# Scoreboard_Wifi_Controller_20170514.net
KiCad netlist of a schematic drawn in EAGLE
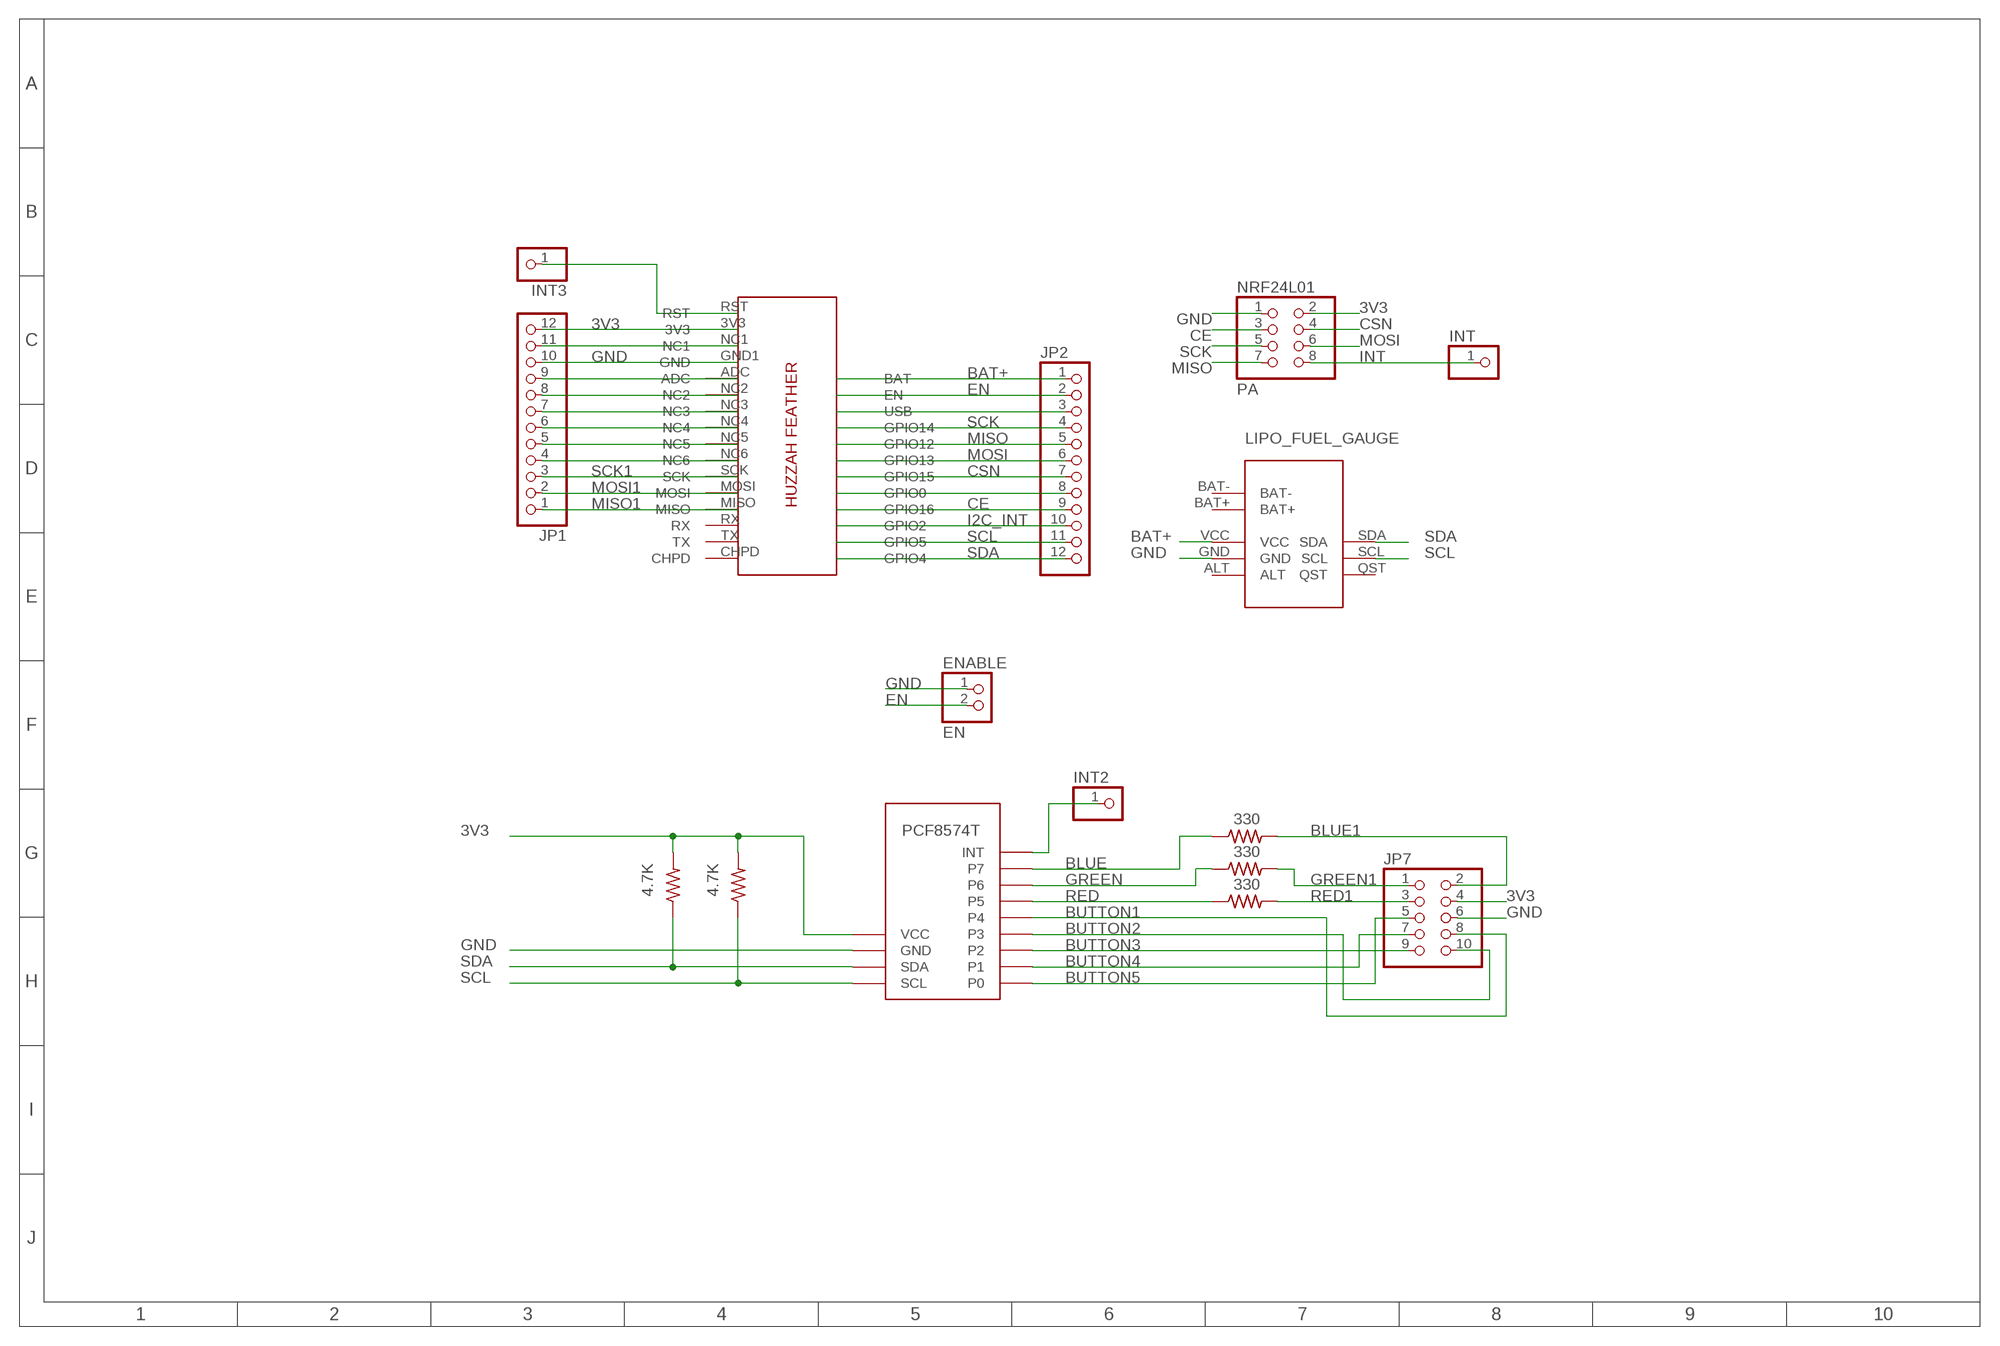
[diagram p0: schematic, sheet 1]

(export (version "E")
  (design (tool "Eeschema 10.0.6"))
  (components
    (comp (ref "ENABLE")
      (value "EN")
      (footprint "eagle-import:1X02_90")
      (libsource (lib "eagle-import") (part "PINHD-1X2/90"))
    )
    (comp (ref "INT")
      (value "PINHD-1X1CB")
      (footprint "eagle-import:1X01-CLEANBIG")
      (libsource (lib "eagle-import") (part "PINHD-1X1CB"))
    )
    (comp (ref "INT2")
      (value "PINHD-1X1CB")
      (footprint "eagle-import:1X01-CLEANBIG")
      (libsource (lib "eagle-import") (part "PINHD-1X1CB"))
    )
    (comp (ref "INT3")
      (value "PINHD-1X1CB")
      (footprint "eagle-import:1X01-CLEANBIG")
      (libsource (lib "eagle-import") (part "PINHD-1X1CB"))
    )
    (comp (ref "JP1")
      (value "PINHD-1X12-CB")
      (footprint "eagle-import:1X12-CB")
      (libsource (lib "eagle-import") (part "PINHD-1X12-CB"))
    )
    (comp (ref "JP2")
      (value "PINHD-1X12-CB")
      (footprint "eagle-import:1X12-CB")
      (libsource (lib "eagle-import") (part "PINHD-1X12-CB"))
    )
    (comp (ref "JP7")
      (value "PINHD-2X5/90")
      (footprint "eagle-import:2X05_90")
      (libsource (lib "eagle-import") (part "PINHD-2X5/90"))
    )
    (comp (ref "LIPO_FUEL_GAUGE")
      (value "LIPO_FUEL_GAUGE")
      (footprint "eagle-import:LIPO_FUEL_GAUGE")
      (libsource (lib "eagle-import") (part "LIPO_FUEL_GAUGE"))
    )
    (comp (ref "NRF24L01")
      (value "PA")
      (footprint "eagle-import:2X04_90")
      (libsource (lib "eagle-import") (part "PINHD-2X4/90"))
    )
    (comp (ref "R2")
      (value "330")
      (footprint "eagle-import:0207_10")
      (libsource (lib "eagle-import") (part "R-US_0207/10"))
    )
    (comp (ref "R3")
      (value "330")
      (footprint "eagle-import:0207_10")
      (libsource (lib "eagle-import") (part "R-US_0207/10"))
    )
    (comp (ref "R4")
      (value "330")
      (footprint "eagle-import:0207_10")
      (libsource (lib "eagle-import") (part "R-US_0207/10"))
    )
    (comp (ref "R5")
      (value "4.7K")
      (footprint "eagle-import:0207_10")
      (libsource (lib "eagle-import") (part "R-US_0207/10"))
    )
    (comp (ref "R6")
      (value "4.7K")
      (footprint "eagle-import:0207_10")
      (libsource (lib "eagle-import") (part "R-US_0207/10"))
    )
    (comp (ref "U$1")
      (value "ADAFRUIT-FEATHER-ESP8266-HUZZAHALT")
      (footprint "eagle-import:ADAFRUIT-FEATHER-ESP8266-HUZZAH-ALT")
      (libsource (lib "eagle-import") (part "ADAFRUIT-FEATHER-ESP8266-HUZZAHALT"))
    )
    (comp (ref "U$3")
      (value "PCF8574T_IO_EXPANDER")
      (footprint "eagle-import:PCF8574T_IO_EXPANDER")
      (libsource (lib "eagle-import") (part "PCF8574T_IO_EXPANDER"))
    )
  )
  (nets
    (net (code "1") (name "/3V3") (class "Default")
      (node (ref "JP1") (pin "12") (pinfunction "12_12") (pintype "passive"))
      (node (ref "JP7") (pin "4") (pinfunction "4_4") (pintype "passive"))
      (node (ref "NRF24L01") (pin "2") (pinfunction "2_2") (pintype "passive"))
      (node (ref "R5") (pin "2") (pinfunction "2_2") (pintype "passive"))
      (node (ref "R6") (pin "2") (pinfunction "2_2") (pintype "passive"))
      (node (ref "U$1") (pin "3V3") (pinfunction "3V3_3V3") (pintype "bidirectional"))
      (node (ref "U$3") (pin "VCC") (pinfunction "VCC_VCC") (pintype "input"))
    )
    (net (code "2") (name "/BAT+") (class "Default")
      (node (ref "JP2") (pin "1") (pinfunction "1_1") (pintype "passive"))
      (node (ref "LIPO_FUEL_GAUGE") (pin "VCC") (pinfunction "VCC_VCC") (pintype "bidirectional"))
      (node (ref "U$1") (pin "BAT") (pinfunction "BAT_BAT") (pintype "bidirectional"))
    )
    (net (code "3") (name "/BLUE") (class "Default")
      (node (ref "R2") (pin "1") (pinfunction "1_1") (pintype "passive"))
      (node (ref "U$3") (pin "P$7") (pinfunction "P7_P$7") (pintype "bidirectional"))
    )
    (net (code "4") (name "/BLUE1") (class "Default")
      (node (ref "JP7") (pin "2") (pinfunction "2_2") (pintype "passive"))
      (node (ref "R2") (pin "2") (pinfunction "2_2") (pintype "passive"))
    )
    (net (code "5") (name "/BUTTON1") (class "Default")
      (node (ref "JP7") (pin "8") (pinfunction "8_8") (pintype "passive"))
      (node (ref "U$3") (pin "P$4") (pinfunction "P4_P$4") (pintype "bidirectional"))
    )
    (net (code "6") (name "/BUTTON2") (class "Default")
      (node (ref "JP7") (pin "10") (pinfunction "10_10") (pintype "passive"))
      (node (ref "U$3") (pin "P$3") (pinfunction "P3_P$3") (pintype "bidirectional"))
    )
    (net (code "7") (name "/BUTTON3") (class "Default")
      (node (ref "JP7") (pin "9") (pinfunction "9_9") (pintype "passive"))
      (node (ref "U$3") (pin "P$2") (pinfunction "P2_P$2") (pintype "bidirectional"))
    )
    (net (code "8") (name "/BUTTON4") (class "Default")
      (node (ref "JP7") (pin "7") (pinfunction "7_7") (pintype "passive"))
      (node (ref "U$3") (pin "P$1") (pinfunction "P1_P$1") (pintype "bidirectional"))
    )
    (net (code "9") (name "/BUTTON5") (class "Default")
      (node (ref "JP7") (pin "5") (pinfunction "5_5") (pintype "passive"))
      (node (ref "U$3") (pin "P$0") (pinfunction "P0_P$0") (pintype "bidirectional"))
    )
    (net (code "10") (name "/CE") (class "Default")
      (node (ref "JP2") (pin "9") (pinfunction "9_9") (pintype "passive"))
      (node (ref "NRF24L01") (pin "3") (pinfunction "3_3") (pintype "passive"))
      (node (ref "U$1") (pin "GPIO16") (pinfunction "GPIO16_GPIO16") (pintype "bidirectional"))
    )
    (net (code "11") (name "/CSN") (class "Default")
      (node (ref "JP2") (pin "7") (pinfunction "7_7") (pintype "passive"))
      (node (ref "NRF24L01") (pin "4") (pinfunction "4_4") (pintype "passive"))
      (node (ref "U$1") (pin "GPIO15") (pinfunction "GPIO15_GPIO15") (pintype "bidirectional"))
    )
    (net (code "12") (name "/EN") (class "Default")
      (node (ref "ENABLE") (pin "2") (pinfunction "2_2") (pintype "passive"))
      (node (ref "JP2") (pin "2") (pinfunction "2_2") (pintype "passive"))
      (node (ref "U$1") (pin "EN") (pinfunction "EN_EN") (pintype "bidirectional"))
    )
    (net (code "13") (name "/GND") (class "Default")
      (node (ref "ENABLE") (pin "1") (pinfunction "1_1") (pintype "passive"))
      (node (ref "JP1") (pin "10") (pinfunction "10_10") (pintype "passive"))
      (node (ref "JP7") (pin "6") (pinfunction "6_6") (pintype "passive"))
      (node (ref "LIPO_FUEL_GAUGE") (pin "GND") (pinfunction "GND_GND") (pintype "bidirectional"))
      (node (ref "NRF24L01") (pin "1") (pinfunction "1_1") (pintype "passive"))
      (node (ref "U$1") (pin "GND1") (pinfunction "GND_GND1") (pintype "bidirectional"))
      (node (ref "U$3") (pin "GND") (pinfunction "GND_GND") (pintype "input"))
    )
    (net (code "14") (name "/GREEN") (class "Default")
      (node (ref "R3") (pin "1") (pinfunction "1_1") (pintype "passive"))
      (node (ref "U$3") (pin "P$6") (pinfunction "P6_P$6") (pintype "bidirectional"))
    )
    (net (code "15") (name "/GREEN1") (class "Default")
      (node (ref "JP7") (pin "1") (pinfunction "1_1") (pintype "passive"))
      (node (ref "R3") (pin "2") (pinfunction "2_2") (pintype "passive"))
    )
    (net (code "16") (name "/I2C_INT") (class "Default")
      (node (ref "INT2") (pin "1") (pinfunction "1_1") (pintype "passive"))
      (node (ref "JP2") (pin "10") (pinfunction "10_10") (pintype "passive"))
      (node (ref "U$1") (pin "GPIO2") (pinfunction "GPIO2_GPIO2") (pintype "bidirectional"))
      (node (ref "U$3") (pin "INT") (pinfunction "INT_INT") (pintype "bidirectional"))
    )
    (net (code "17") (name "/INT") (class "Default")
      (node (ref "INT") (pin "1") (pinfunction "1_1") (pintype "passive"))
      (node (ref "NRF24L01") (pin "8") (pinfunction "8_8") (pintype "passive"))
    )
    (net (code "18") (name "/MISO") (class "Default")
      (node (ref "JP2") (pin "5") (pinfunction "5_5") (pintype "passive"))
      (node (ref "NRF24L01") (pin "7") (pinfunction "7_7") (pintype "passive"))
      (node (ref "U$1") (pin "GPIO12") (pinfunction "GPIO12_GPIO12") (pintype "bidirectional"))
    )
    (net (code "19") (name "/MISO1") (class "Default")
      (node (ref "JP1") (pin "1") (pinfunction "1_1") (pintype "passive"))
      (node (ref "U$1") (pin "MISO") (pinfunction "MISO_MISO") (pintype "bidirectional"))
    )
    (net (code "20") (name "/MOSI") (class "Default")
      (node (ref "JP2") (pin "6") (pinfunction "6_6") (pintype "passive"))
      (node (ref "NRF24L01") (pin "6") (pinfunction "6_6") (pintype "passive"))
      (node (ref "U$1") (pin "GPIO13") (pinfunction "GPIO13_GPIO13") (pintype "bidirectional"))
    )
    (net (code "21") (name "/MOSI1") (class "Default")
      (node (ref "JP1") (pin "2") (pinfunction "2_2") (pintype "passive"))
      (node (ref "U$1") (pin "MOSI") (pinfunction "MOSI_MOSI") (pintype "bidirectional"))
    )
    (net (code "22") (name "/RED") (class "Default")
      (node (ref "R4") (pin "1") (pinfunction "1_1") (pintype "passive"))
      (node (ref "U$3") (pin "P$5") (pinfunction "P5_P$5") (pintype "bidirectional"))
    )
    (net (code "23") (name "/RED1") (class "Default")
      (node (ref "JP7") (pin "3") (pinfunction "3_3") (pintype "passive"))
      (node (ref "R4") (pin "2") (pinfunction "2_2") (pintype "passive"))
    )
    (net (code "24") (name "/SCK") (class "Default")
      (node (ref "JP2") (pin "4") (pinfunction "4_4") (pintype "passive"))
      (node (ref "NRF24L01") (pin "5") (pinfunction "5_5") (pintype "passive"))
      (node (ref "U$1") (pin "GPIO14") (pinfunction "GPIO14_GPIO14") (pintype "bidirectional"))
    )
    (net (code "25") (name "/SCK1") (class "Default")
      (node (ref "JP1") (pin "3") (pinfunction "3_3") (pintype "passive"))
      (node (ref "U$1") (pin "SCK") (pinfunction "SCK_SCK") (pintype "bidirectional"))
    )
    (net (code "26") (name "/SCL") (class "Default")
      (node (ref "JP2") (pin "11") (pinfunction "11_11") (pintype "passive"))
      (node (ref "LIPO_FUEL_GAUGE") (pin "SCL") (pinfunction "SCL_SCL") (pintype "bidirectional"))
      (node (ref "R5") (pin "1") (pinfunction "1_1") (pintype "passive"))
      (node (ref "U$1") (pin "GPIO5") (pinfunction "GPIO5_GPIO5") (pintype "bidirectional"))
      (node (ref "U$3") (pin "SCL") (pinfunction "SCL_SCL") (pintype "bidirectional"))
    )
    (net (code "27") (name "/SDA") (class "Default")
      (node (ref "JP2") (pin "12") (pinfunction "12_12") (pintype "passive"))
      (node (ref "LIPO_FUEL_GAUGE") (pin "SDA") (pinfunction "SDA_SDA") (pintype "bidirectional"))
      (node (ref "R6") (pin "1") (pinfunction "1_1") (pintype "passive"))
      (node (ref "U$1") (pin "GPIO4") (pinfunction "GPIO4_GPIO4") (pintype "bidirectional"))
      (node (ref "U$3") (pin "SDA") (pinfunction "SDA_SDA") (pintype "bidirectional"))
    )
    (net (code "28") (name "Net-(INT3-Pad1)") (class "Default")
      (node (ref "INT3") (pin "1") (pinfunction "1_1") (pintype "passive"))
      (node (ref "U$1") (pin "RST") (pinfunction "RST_RST") (pintype "bidirectional"))
    )
    (net (code "29") (name "Net-(JP1-Pad4)") (class "Default")
      (node (ref "JP1") (pin "4") (pinfunction "4_4") (pintype "passive"))
      (node (ref "U$1") (pin "NC6") (pinfunction "NC6_NC6") (pintype "bidirectional"))
    )
    (net (code "30") (name "Net-(JP1-Pad5)") (class "Default")
      (node (ref "JP1") (pin "5") (pinfunction "5_5") (pintype "passive"))
      (node (ref "U$1") (pin "NC5") (pinfunction "NC5_NC5") (pintype "bidirectional"))
    )
    (net (code "31") (name "Net-(JP1-Pad6)") (class "Default")
      (node (ref "JP1") (pin "6") (pinfunction "6_6") (pintype "passive"))
      (node (ref "U$1") (pin "NC4") (pinfunction "NC4_NC4") (pintype "bidirectional"))
    )
    (net (code "32") (name "Net-(JP1-Pad7)") (class "Default")
      (node (ref "JP1") (pin "7") (pinfunction "7_7") (pintype "passive"))
      (node (ref "U$1") (pin "NC3") (pinfunction "NC3_NC3") (pintype "bidirectional"))
    )
    (net (code "33") (name "Net-(JP1-Pad8)") (class "Default")
      (node (ref "JP1") (pin "8") (pinfunction "8_8") (pintype "passive"))
      (node (ref "U$1") (pin "NC2") (pinfunction "NC2_NC2") (pintype "bidirectional"))
    )
    (net (code "34") (name "Net-(JP1-Pad9)") (class "Default")
      (node (ref "JP1") (pin "9") (pinfunction "9_9") (pintype "passive"))
      (node (ref "U$1") (pin "ADC") (pinfunction "ADC_ADC") (pintype "bidirectional"))
    )
    (net (code "35") (name "Net-(JP1-Pad11)") (class "Default")
      (node (ref "JP1") (pin "11") (pinfunction "11_11") (pintype "passive"))
      (node (ref "U$1") (pin "NC1") (pinfunction "NC1_NC1") (pintype "bidirectional"))
    )
    (net (code "36") (name "Net-(JP2-Pad3)") (class "Default")
      (node (ref "JP2") (pin "3") (pinfunction "3_3") (pintype "passive"))
      (node (ref "U$1") (pin "USB") (pinfunction "USB_USB") (pintype "bidirectional"))
    )
    (net (code "37") (name "Net-(JP2-Pad8)") (class "Default")
      (node (ref "JP2") (pin "8") (pinfunction "8_8") (pintype "passive"))
      (node (ref "U$1") (pin "GPIO0") (pinfunction "GPIO0_GPIO0") (pintype "bidirectional"))
    )
    (net (code "38") (name "unconnected-(LIPO_FUEL_GAUGE-PadALT)") (class "Default")
      (node (ref "LIPO_FUEL_GAUGE") (pin "ALT") (pinfunction "ALT_ALT") (pintype "bidirectional"))
    )
    (net (code "39") (name "unconnected-(LIPO_FUEL_GAUGE-PadBAT+)") (class "Default")
      (node (ref "LIPO_FUEL_GAUGE") (pin "BAT+") (pinfunction "BAT+_BAT+") (pintype "bidirectional"))
    )
    (net (code "40") (name "unconnected-(LIPO_FUEL_GAUGE-PadBAT-)") (class "Default")
      (node (ref "LIPO_FUEL_GAUGE") (pin "BAT-") (pinfunction "BAT-_BAT-") (pintype "bidirectional"))
    )
    (net (code "41") (name "unconnected-(LIPO_FUEL_GAUGE-PadQST)") (class "Default")
      (node (ref "LIPO_FUEL_GAUGE") (pin "QST") (pinfunction "QST_QST") (pintype "bidirectional"))
    )
    (net (code "42") (name "unconnected-(U$1-PadCHPD)") (class "Default")
      (node (ref "U$1") (pin "CHPD") (pinfunction "CHPD_CHPD") (pintype "bidirectional"))
    )
    (net (code "43") (name "unconnected-(U$1-PadRX)") (class "Default")
      (node (ref "U$1") (pin "RX") (pinfunction "RX_RX") (pintype "bidirectional"))
    )
    (net (code "44") (name "unconnected-(U$1-PadTX)") (class "Default")
      (node (ref "U$1") (pin "TX") (pinfunction "TX_TX") (pintype "bidirectional"))
    )
  )
)
